# ICSP_Burn_Buffer.net
KiCad netlist of a schematic drawn in Altium Designer
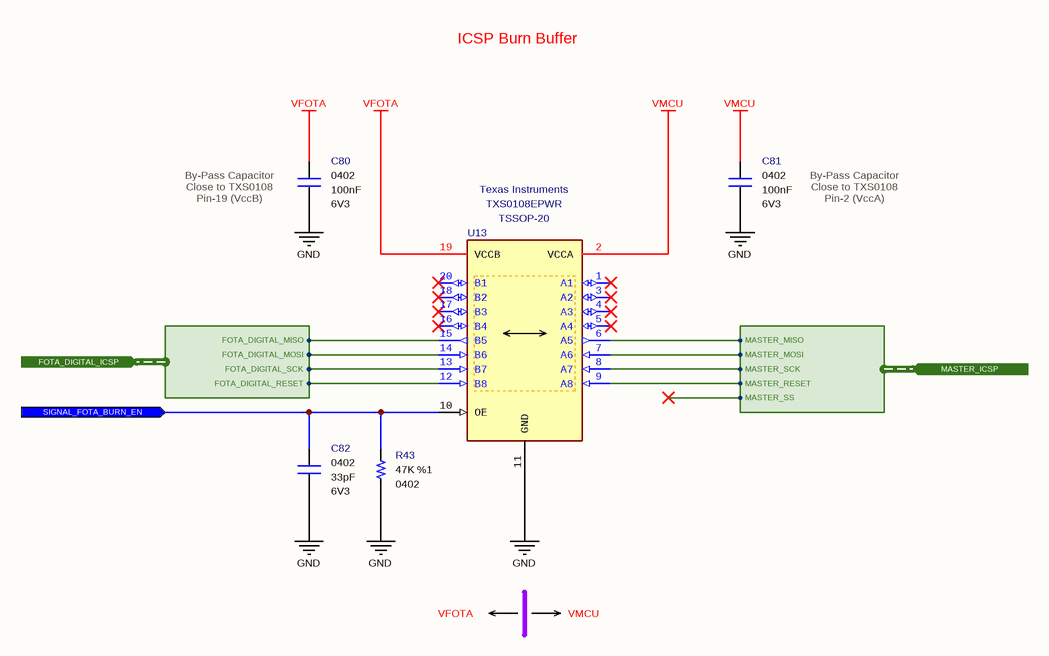
[diagram p0: ICSP Burn Buffer.SchDoc]

(export (version "E")
  (design (tool "Eeschema 10.0.6"))
  (components
    (comp (ref "C80")
      (value "100nF")
      (footprint "CAPACITOR_0402")
      (description "Capacitor - 100nF [0402-6V3] (Ceramic)")
      (fields
        (field (name "TOLERANCE") "%10")
        (field (name "CASE") "0402")
        (field (name "VOLTAGE") "6V3")
        (field (name "MANUFACTURER PART NUMBER") "04026D104KAT4A")
      )
      (libsource (lib "Ovoo_Library") (part "Capacitor - 100nF [0402-6V3]"))
    )
    (comp (ref "C81")
      (value "100nF")
      (footprint "CAPACITOR_0402")
      (description "Capacitor - 100nF [0402-6V3] (Ceramic)")
      (fields
        (field (name "TOLERANCE") "%10")
        (field (name "CASE") "0402")
        (field (name "VOLTAGE") "6V3")
        (field (name "MANUFACTURER PART NUMBER") "04026D104KAT4A")
      )
      (libsource (lib "Ovoo_Library") (part "Capacitor - 100nF [0402-6V3]"))
    )
    (comp (ref "C82")
      (value "33pF")
      (footprint "CAPACITOR_0402")
      (description "Capacitor - 33pF [0402] (Ceramic)")
      (fields
        (field (name "CASE") "0402")
        (field (name "TOLERANCE") "10%")
        (field (name "VOLTAGE") "6V3")
        (field (name "MANUFACTURER PART NUMBER") "C0402C330J9RACAUTO")
      )
      (libsource (lib "Ovoo_Library") (part "Capacitor - 33pF [0402-6V3]"))
    )
    (comp (ref "R43")
      (value "47K")
      (footprint "RESISTOR_0402")
      (description "Thick Film Resistors - SMD 1/16 W 47 Kohms 1%")
      (fields
        (field (name "TOLERANCE") "%1")
        (field (name "CASE") "0402")
        (field (name "MANUFACTURER PART NUMBER") "CRCW040247K0FKED")
        (field (name "MOUSER PART NUMBER") "71-CRCW0402-47K-E3")
      )
      (libsource (lib "Ovoo_Library") (part "Resistor - 47K"))
    )
    (comp (ref "U13")
      (value "Voltage Level Shifter")
      (footprint "TSSOP-20")
      (description "Translation - Voltage Levels 8B Bidir Vltg-Level Translator")
      (fields
        (field (name "MOUSER PART NUMBER") "595-TXS0108EPWR")
        (field (name "MANUFACTURER PART NUMBER") "TXS0108EPWR")
        (field (name "CASE") "TSSOP-20")
        (field (name "MANUFACTURER NAME") "Texas Instruments")
      )
      (libsource (lib "Ovoo_Library") (part "IC - TXS0108EPW"))
    )
  )
  (nets
    (net (code "3") (name "/FOTA_DIGITAL_MISO") (class "Default")
      (node (ref "U13") (pin "15") (pinfunction "B5_15") (pintype "output"))
    )
    (net (code "4") (name "/FOTA_DIGITAL_MOSI") (class "Default")
      (node (ref "U13") (pin "14") (pinfunction "B6_14") (pintype "input"))
    )
    (net (code "5") (name "/FOTA_DIGITAL_RESET") (class "Default")
      (node (ref "U13") (pin "12") (pinfunction "B8_12") (pintype "input"))
    )
    (net (code "6") (name "/FOTA_DIGITAL_SCK") (class "Default")
      (node (ref "U13") (pin "13") (pinfunction "B7_13") (pintype "input"))
    )
    (net (code "7") (name "/MASTER_MISO") (class "Default")
      (node (ref "U13") (pin "6") (pinfunction "A5_6") (pintype "output"))
    )
    (net (code "8") (name "/MASTER_MOSI") (class "Default")
      (node (ref "U13") (pin "7") (pinfunction "A6_7") (pintype "input"))
    )
    (net (code "9") (name "/MASTER_RESET") (class "Default")
      (node (ref "U13") (pin "9") (pinfunction "A8_9") (pintype "input"))
    )
    (net (code "10") (name "/MASTER_SCK") (class "Default")
      (node (ref "U13") (pin "8") (pinfunction "A7_8") (pintype "input"))
    )
    (net (code "12") (name "/SIGNAL_FOTA_BURN_EN") (class "Default")
      (node (ref "C82") (pin "1") (pinfunction "1_1") (pintype "passive"))
      (node (ref "R43") (pin "2") (pinfunction "2_2") (pintype "passive"))
      (node (ref "U13") (pin "10") (pinfunction "OE_10") (pintype "input"))
    )
    (net (code "15") (name "GND") (class "Default")
      (node (ref "C80") (pin "1") (pinfunction "1_1") (pintype "passive"))
      (node (ref "C81") (pin "1") (pinfunction "1_1") (pintype "passive"))
      (node (ref "C82") (pin "2") (pinfunction "2_2") (pintype "passive"))
      (node (ref "R43") (pin "1") (pinfunction "1_1") (pintype "passive"))
      (node (ref "U13") (pin "11") (pinfunction "GND_11") (pintype "passive"))
    )
    (net (code "16") (name "VFOTA") (class "Default")
      (node (ref "C80") (pin "2") (pinfunction "2_2") (pintype "passive"))
      (node (ref "U13") (pin "19") (pinfunction "VCCB_19") (pintype "power_in"))
    )
    (net (code "17") (name "VMCU") (class "Default")
      (node (ref "C81") (pin "2") (pinfunction "2_2") (pintype "passive"))
      (node (ref "U13") (pin "2") (pinfunction "VCCA_2") (pintype "power_in"))
    )
    (net (code "18") (name "unconnected-(U13-A1-Pad1)") (class "Default")
      (node (ref "U13") (pin "1") (pinfunction "A1_1") (pintype "bidirectional+no_connect"))
    )
    (net (code "19") (name "unconnected-(U13-A2-Pad3)") (class "Default")
      (node (ref "U13") (pin "3") (pinfunction "A2_3") (pintype "bidirectional+no_connect"))
    )
    (net (code "20") (name "unconnected-(U13-A3-Pad4)") (class "Default")
      (node (ref "U13") (pin "4") (pinfunction "A3_4") (pintype "bidirectional+no_connect"))
    )
    (net (code "21") (name "unconnected-(U13-A4-Pad5)") (class "Default")
      (node (ref "U13") (pin "5") (pinfunction "A4_5") (pintype "bidirectional+no_connect"))
    )
    (net (code "22") (name "unconnected-(U13-B1-Pad20)") (class "Default")
      (node (ref "U13") (pin "20") (pinfunction "B1_20") (pintype "bidirectional+no_connect"))
    )
    (net (code "23") (name "unconnected-(U13-B2-Pad18)") (class "Default")
      (node (ref "U13") (pin "18") (pinfunction "B2_18") (pintype "bidirectional+no_connect"))
    )
    (net (code "24") (name "unconnected-(U13-B3-Pad17)") (class "Default")
      (node (ref "U13") (pin "17") (pinfunction "B3_17") (pintype "bidirectional+no_connect"))
    )
    (net (code "25") (name "unconnected-(U13-B4-Pad16)") (class "Default")
      (node (ref "U13") (pin "16") (pinfunction "B4_16") (pintype "bidirectional+no_connect"))
    )
  )
)
